# Sheet1.net
KiCad netlist of a schematic drawn in Altium Designer
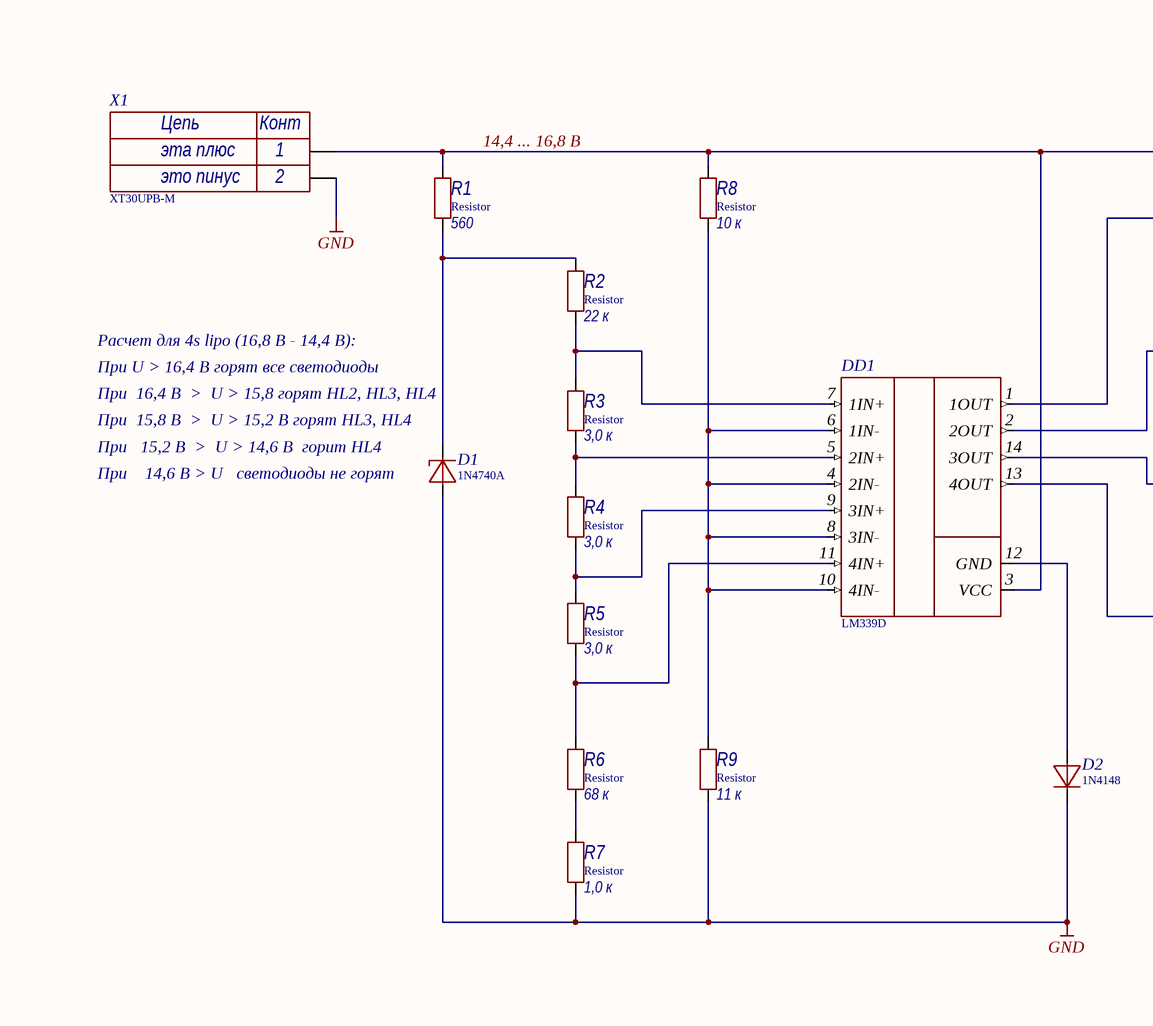
[diagram p0: Sheet1.SchDoc, left]
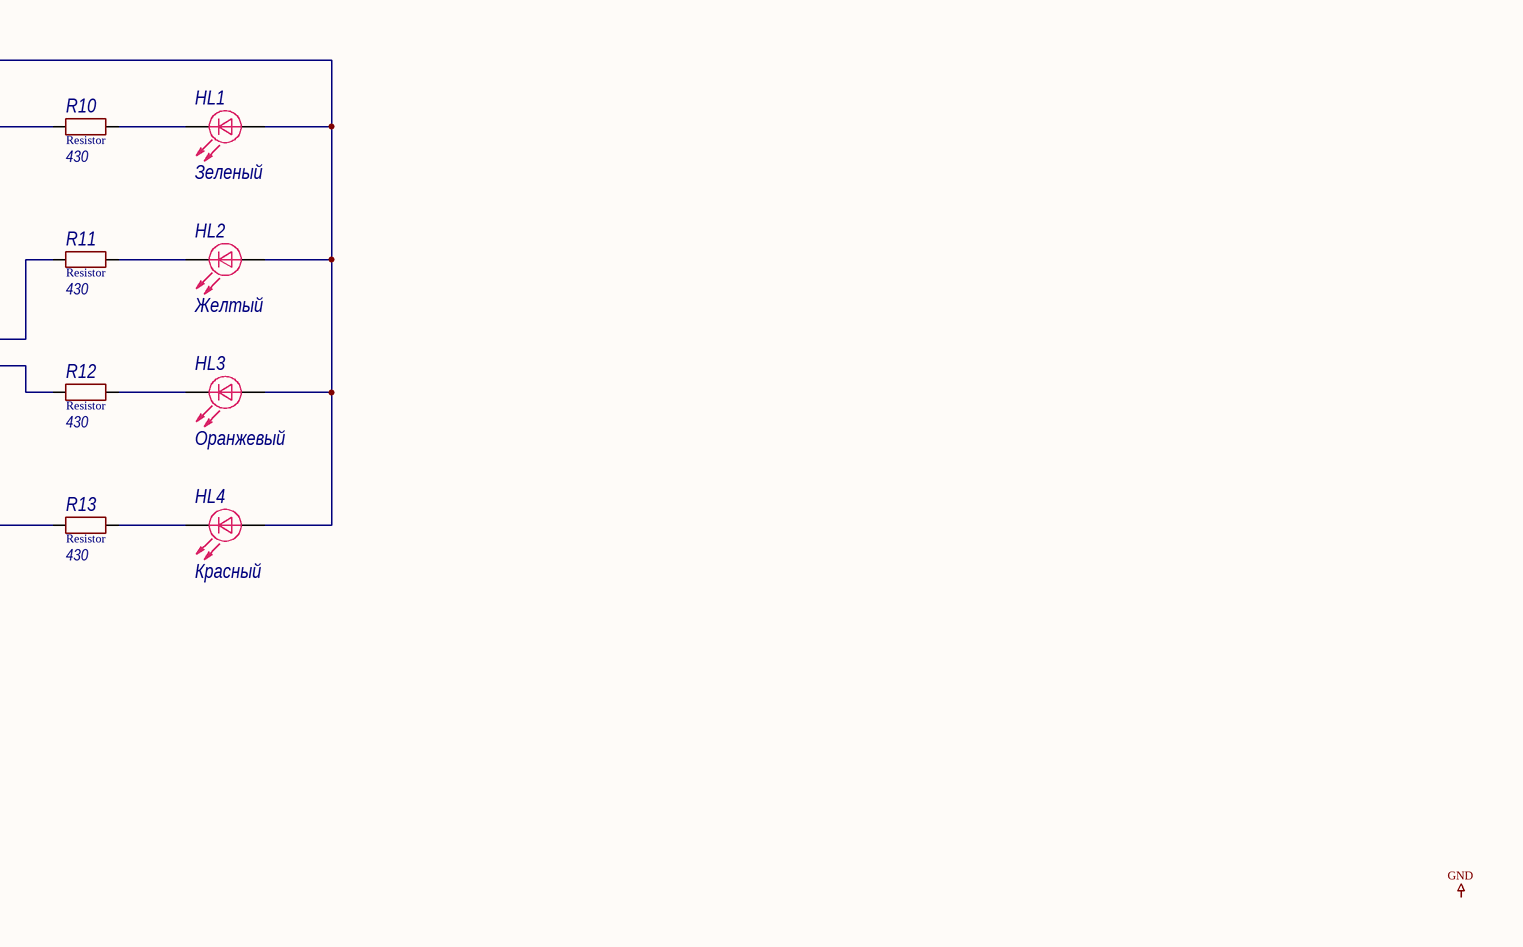
[diagram p1: Sheet1.SchDoc, right]

(export (version "E")
  (design (tool "Eeschema 10.0.6"))
  (components
    (comp (ref "D1")
      (value "1N4740A")
      (footprint "DIOAD1060W70L435D230")
      (description "диод Зенера 10 В")
      (fields (field (name "MF") "Vishay Semiconductor") (field (name "MP") "1N4740A-TR"))
      (libsource (lib "Hydrolib") (part "1N4740A"))
    )
    (comp (ref "D2")
      (value "1N4148")
      (footprint "DIOAD753W49L380D172B")
      (description "диод")
      (fields (field (name "MF") "ON Semiconductor"))
      (libsource (lib "Hydrolib") (part "1N4148"))
    )
    (comp (ref "DD1")
      (value "LM339D")
      (footprint "SOIC127P600X175-14N")
      (description "4 компаратора")
      (fields (field (name "MF") "Texas Instruments"))
      (libsource (lib "Hydrolib") (part "LM339D"))
    )
    (comp (ref "HL1")
      (value "LED")
      (footprint "0805D")
      (description "Светодиод")
      (fields (field (name "COLOR") "Зеленый"))
      (libsource (lib "Hydrolib") (part "LED"))
    )
    (comp (ref "HL2")
      (value "LED")
      (footprint "0805D")
      (description "Светодиод")
      (fields (field (name "COLOR") "Желтый"))
      (libsource (lib "Hydrolib") (part "LED"))
    )
    (comp (ref "HL3")
      (value "LED")
      (footprint "0805D")
      (description "Светодиод")
      (fields (field (name "COLOR") "Оранжевый"))
      (libsource (lib "Hydrolib") (part "LED"))
    )
    (comp (ref "HL4")
      (value "LED")
      (footprint "0805D")
      (description "Светодиод")
      (fields (field (name "COLOR") "Красный"))
      (libsource (lib "Hydrolib") (part "LED"))
    )
    (comp (ref "R1")
      (value "Resistor")
      (footprint "0603R")
      (description "Резистор номиналом 560 Ом и точностью 1%")
      (fields
        (field (name "ALTIUM_VALUE") "560")
        (field (name "PART NUMBER") "Resistor_560_1_0603")
        (field (name "TOLERANCE") "1%")
      )
      (libsource (lib "Hydrolib") (part "Resistor"))
    )
    (comp (ref "R2")
      (value "Resistor")
      (footprint "0603R")
      (description "Резистор номиналом 22 кОм и точностью 1%")
      (fields
        (field (name "ALTIUM_VALUE") "22 к")
        (field (name "PART NUMBER") "Resistor_22k_1_0603")
        (field (name "TOLERANCE") "1%")
      )
      (libsource (lib "Hydrolib") (part "Resistor"))
    )
    (comp (ref "R3")
      (value "Resistor")
      (footprint "0603R")
      (description "Резистор номиналом 3,0 кОм и точностью 1%")
      (fields
        (field (name "ALTIUM_VALUE") "3,0 к")
        (field (name "PART NUMBER") "Resistor_3.0k_1_0603")
        (field (name "TOLERANCE") "1%")
      )
      (libsource (lib "Hydrolib") (part "Resistor"))
    )
    (comp (ref "R4")
      (value "Resistor")
      (footprint "0603R")
      (description "Резистор номиналом 3,0 кОм и точностью 1%")
      (fields
        (field (name "ALTIUM_VALUE") "3,0 к")
        (field (name "PART NUMBER") "Resistor_3.0k_1_0603")
        (field (name "TOLERANCE") "1%")
      )
      (libsource (lib "Hydrolib") (part "Resistor"))
    )
    (comp (ref "R5")
      (value "Resistor")
      (footprint "0603R")
      (description "Резистор номиналом 3,0 кОм и точностью 1%")
      (fields
        (field (name "ALTIUM_VALUE") "3,0 к")
        (field (name "PART NUMBER") "Resistor_3.0k_1_0603")
        (field (name "TOLERANCE") "1%")
      )
      (libsource (lib "Hydrolib") (part "Resistor"))
    )
    (comp (ref "R6")
      (value "Resistor")
      (footprint "0603R")
      (description "Резистор номиналом 68 кОм и точностью 1%")
      (fields
        (field (name "ALTIUM_VALUE") "68 к")
        (field (name "PART NUMBER") "Resistor_68k_1_0603")
        (field (name "TOLERANCE") "1%")
      )
      (libsource (lib "Hydrolib") (part "Resistor"))
    )
    (comp (ref "R7")
      (value "Resistor")
      (footprint "0603R")
      (description "Резистор номиналом 1,0 кОм и точностью 1%")
      (fields
        (field (name "ALTIUM_VALUE") "1,0 к")
        (field (name "PART NUMBER") "Resistor_1.0k_1_0603")
        (field (name "TOLERANCE") "1%")
      )
      (libsource (lib "Hydrolib") (part "Resistor"))
    )
    (comp (ref "R8")
      (value "Resistor")
      (footprint "0603R")
      (description "Резистор номиналом 10 кОм и точностью 1%")
      (fields
        (field (name "ALTIUM_VALUE") "10 к")
        (field (name "PART NUMBER") "Resistor_10k_1_0603")
        (field (name "TOLERANCE") "1%")
      )
      (libsource (lib "Hydrolib") (part "Resistor"))
    )
    (comp (ref "R9")
      (value "Resistor")
      (footprint "0603R")
      (description "Резистор номиналом 11 кОм и точностью 1%")
      (fields
        (field (name "ALTIUM_VALUE") "11 к")
        (field (name "PART NUMBER") "Resistor_11k_1_0603")
        (field (name "TOLERANCE") "1%")
      )
      (libsource (lib "Hydrolib") (part "Resistor"))
    )
    (comp (ref "R10")
      (value "Resistor")
      (footprint "0603R")
      (description "Резистор номиналом 430 Ом и точностью 1%")
      (fields
        (field (name "ALTIUM_VALUE") "430")
        (field (name "PART NUMBER") "Resistor_430_1_0603")
        (field (name "TOLERANCE") "1%")
      )
      (libsource (lib "") (part "Resistor_1"))
    )
    (comp (ref "R11")
      (value "Resistor")
      (footprint "0603R")
      (description "Резистор номиналом 430 Ом и точностью 1%")
      (fields
        (field (name "ALTIUM_VALUE") "430")
        (field (name "PART NUMBER") "Resistor_430_1_0603")
        (field (name "TOLERANCE") "1%")
      )
      (libsource (lib "") (part "Resistor_1"))
    )
    (comp (ref "R12")
      (value "Resistor")
      (footprint "0603R")
      (description "Резистор номиналом 430 Ом и точностью 1%")
      (fields
        (field (name "ALTIUM_VALUE") "430")
        (field (name "PART NUMBER") "Resistor_430_1_0603")
        (field (name "TOLERANCE") "1%")
      )
      (libsource (lib "") (part "Resistor_1"))
    )
    (comp (ref "R13")
      (value "Resistor")
      (footprint "0603R")
      (description "Резистор номиналом 430 Ом и точностью 1%")
      (fields
        (field (name "ALTIUM_VALUE") "430")
        (field (name "PART NUMBER") "Resistor_430_1_0603")
        (field (name "TOLERANCE") "1%")
      )
      (libsource (lib "") (part "Resistor_1"))
    )
    (comp (ref "X1")
      (value "XT30UPB-M")
      (footprint "XT30UPB-M")
      (description "2-пиновый разъем с ключом")
      (fields (field (name "VALUE2") "это пинус") (field (name "VALUE1") "эта плюс"))
      (libsource (lib "Hydrolib") (part "Polar_Conn"))
    )
  )
  (nets
    (net (code "1") (name "/14,4 ... 16,8 В") (class "Default")
      (node (ref "DD1") (pin "3") (pinfunction "VCC_3") (pintype "power_in"))
      (node (ref "HL1") (pin "1") (pinfunction "1_1") (pintype "passive"))
      (node (ref "HL2") (pin "1") (pinfunction "1_1") (pintype "passive"))
      (node (ref "HL3") (pin "1") (pinfunction "1_1") (pintype "passive"))
      (node (ref "HL4") (pin "1") (pinfunction "1_1") (pintype "passive"))
      (node (ref "R1") (pin "2") (pinfunction "2_2") (pintype "passive"))
      (node (ref "R8") (pin "2") (pinfunction "2_2") (pintype "passive"))
      (node (ref "X1") (pin "P") (pinfunction "P_P") (pintype "passive"))
    )
    (net (code "2") (name "GND") (class "Default")
      (node (ref "D1") (pin "A") (pinfunction "A_A") (pintype "passive"))
      (node (ref "D2") (pin "K") (pinfunction "K_K") (pintype "passive"))
      (node (ref "R7") (pin "1") (pinfunction "1_1") (pintype "passive"))
      (node (ref "R9") (pin "1") (pinfunction "1_1") (pintype "passive"))
      (node (ref "X1") (pin "N") (pinfunction "N_N") (pintype "passive"))
    )
    (net (code "3") (name "Net-(D1-K)") (class "Default")
      (node (ref "D1") (pin "C") (pinfunction "K_C") (pintype "passive"))
      (node (ref "R1") (pin "1") (pinfunction "1_1") (pintype "passive"))
      (node (ref "R2") (pin "2") (pinfunction "2_2") (pintype "passive"))
    )
    (net (code "4") (name "Net-(DD1-1IN+)") (class "Default")
      (node (ref "DD1") (pin "7") (pinfunction "1IN+_7") (pintype "input"))
      (node (ref "R2") (pin "1") (pinfunction "1_1") (pintype "passive"))
      (node (ref "R3") (pin "2") (pinfunction "2_2") (pintype "passive"))
    )
    (net (code "5") (name "Net-(DD1-1IN-)") (class "Default")
      (node (ref "DD1") (pin "10") (pinfunction "4IN-_10") (pintype "input"))
      (node (ref "DD1") (pin "4") (pinfunction "2IN-_4") (pintype "input"))
      (node (ref "DD1") (pin "6") (pinfunction "1IN-_6") (pintype "input"))
      (node (ref "DD1") (pin "8") (pinfunction "3IN-_8") (pintype "input"))
      (node (ref "R8") (pin "1") (pinfunction "1_1") (pintype "passive"))
      (node (ref "R9") (pin "2") (pinfunction "2_2") (pintype "passive"))
    )
    (net (code "6") (name "Net-(DD1-1OUT)") (class "Default")
      (node (ref "DD1") (pin "1") (pinfunction "1OUT_1") (pintype "output"))
      (node (ref "R10") (pin "1") (pinfunction "1_1") (pintype "passive"))
    )
    (net (code "7") (name "Net-(DD1-2IN+)") (class "Default")
      (node (ref "DD1") (pin "5") (pinfunction "2IN+_5") (pintype "input"))
      (node (ref "R3") (pin "1") (pinfunction "1_1") (pintype "passive"))
      (node (ref "R4") (pin "2") (pinfunction "2_2") (pintype "passive"))
    )
    (net (code "8") (name "Net-(DD1-2OUT)") (class "Default")
      (node (ref "DD1") (pin "2") (pinfunction "2OUT_2") (pintype "output"))
      (node (ref "R11") (pin "1") (pinfunction "1_1") (pintype "passive"))
    )
    (net (code "9") (name "Net-(DD1-3IN+)") (class "Default")
      (node (ref "DD1") (pin "9") (pinfunction "3IN+_9") (pintype "input"))
      (node (ref "R4") (pin "1") (pinfunction "1_1") (pintype "passive"))
      (node (ref "R5") (pin "2") (pinfunction "2_2") (pintype "passive"))
    )
    (net (code "10") (name "Net-(DD1-3OUT)") (class "Default")
      (node (ref "DD1") (pin "14") (pinfunction "3OUT_14") (pintype "output"))
      (node (ref "R12") (pin "1") (pinfunction "1_1") (pintype "passive"))
    )
    (net (code "11") (name "Net-(DD1-4IN+)") (class "Default")
      (node (ref "DD1") (pin "11") (pinfunction "4IN+_11") (pintype "input"))
      (node (ref "R5") (pin "1") (pinfunction "1_1") (pintype "passive"))
      (node (ref "R6") (pin "2") (pinfunction "2_2") (pintype "passive"))
    )
    (net (code "12") (name "Net-(DD1-4OUT)") (class "Default")
      (node (ref "DD1") (pin "13") (pinfunction "4OUT_13") (pintype "output"))
      (node (ref "R13") (pin "1") (pinfunction "1_1") (pintype "passive"))
    )
    (net (code "13") (name "Net-(DD1-GND)") (class "Default")
      (node (ref "D2") (pin "A") (pinfunction "A_A") (pintype "passive"))
      (node (ref "DD1") (pin "12") (pinfunction "GND_12") (pintype "power_in"))
    )
    (net (code "14") (name "Net-(HL1-Pad2)") (class "Default")
      (node (ref "HL1") (pin "2") (pinfunction "2_2") (pintype "passive"))
      (node (ref "R10") (pin "2") (pinfunction "2_2") (pintype "passive"))
    )
    (net (code "15") (name "Net-(HL2-Pad2)") (class "Default")
      (node (ref "HL2") (pin "2") (pinfunction "2_2") (pintype "passive"))
      (node (ref "R11") (pin "2") (pinfunction "2_2") (pintype "passive"))
    )
    (net (code "16") (name "Net-(HL3-Pad2)") (class "Default")
      (node (ref "HL3") (pin "2") (pinfunction "2_2") (pintype "passive"))
      (node (ref "R12") (pin "2") (pinfunction "2_2") (pintype "passive"))
    )
    (net (code "17") (name "Net-(HL4-Pad2)") (class "Default")
      (node (ref "HL4") (pin "2") (pinfunction "2_2") (pintype "passive"))
      (node (ref "R13") (pin "2") (pinfunction "2_2") (pintype "passive"))
    )
    (net (code "18") (name "Net-(R6-Pad1)") (class "Default")
      (node (ref "R6") (pin "1") (pinfunction "1_1") (pintype "passive"))
      (node (ref "R7") (pin "2") (pinfunction "2_2") (pintype "passive"))
    )
  )
)
